# Adafruit_Feather_M0_Express_test.net
KiCad netlist of a schematic drawn in EAGLE
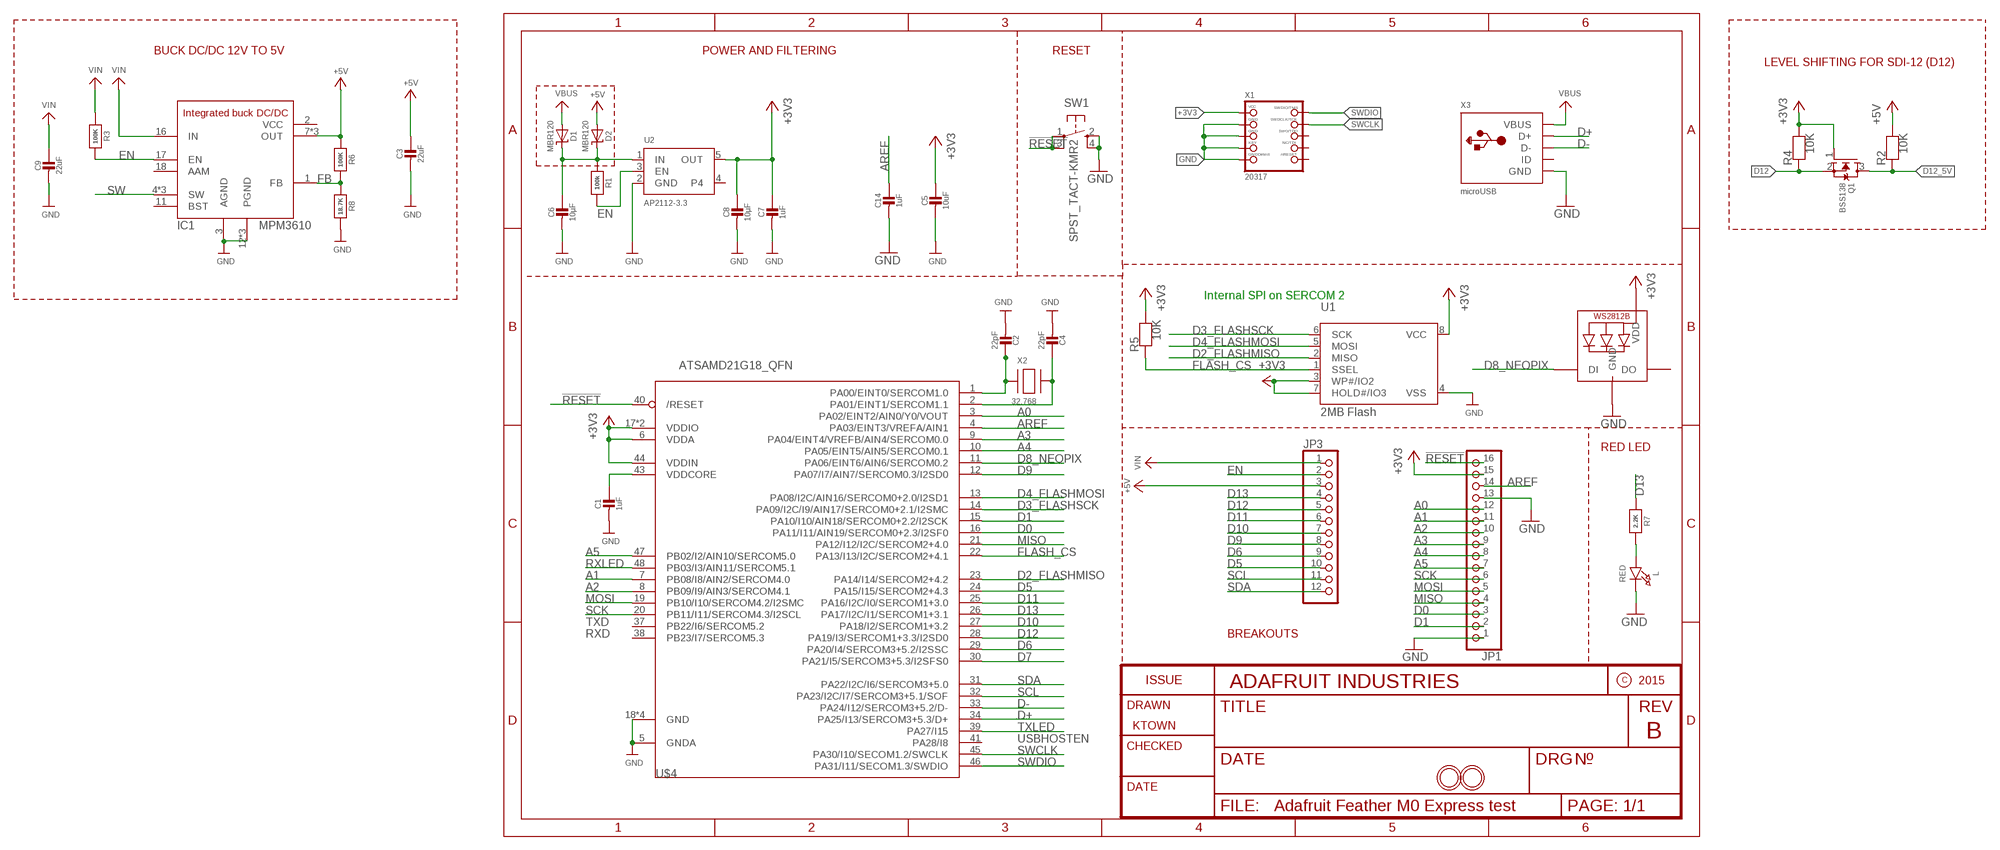
[diagram p0: schematic, sheet 1]

(export (version "E")
  (design (tool "Eeschema 10.0.6"))
  (components
    (comp (ref "C1")
      (value "1uF")
      (footprint "eagle-import:0603-NO")
      (libsource (lib "eagle-import") (part "CAP_CERAMIC0603_NO"))
    )
    (comp (ref "C2")
      (value "22pF")
      (footprint "eagle-import:0603-NO")
      (libsource (lib "eagle-import") (part "CAP_CERAMIC0603_NO"))
    )
    (comp (ref "C3")
      (value "22uF")
      (footprint "eagle-import:0805-NO")
      (libsource (lib "eagle-import") (part "CAP_CERAMIC0805-NOOUTLINE"))
    )
    (comp (ref "C4")
      (value "22pF")
      (footprint "eagle-import:0603-NO")
      (libsource (lib "eagle-import") (part "CAP_CERAMIC0603_NO"))
    )
    (comp (ref "C5")
      (value "10uF")
      (footprint "eagle-import:0805-NO")
      (libsource (lib "eagle-import") (part "CAP_CERAMIC0805-NOOUTLINE"))
    )
    (comp (ref "C6")
      (value "10µF")
      (footprint "eagle-import:0805-NO")
      (libsource (lib "eagle-import") (part "CAP_CERAMIC0805-NOOUTLINE"))
    )
    (comp (ref "C7")
      (value "1uF")
      (footprint "eagle-import:0603-NO")
      (libsource (lib "eagle-import") (part "CAP_CERAMIC0603_NO"))
    )
    (comp (ref "C8")
      (value "10µF")
      (footprint "eagle-import:0805-NO")
      (libsource (lib "eagle-import") (part "CAP_CERAMIC0805-NOOUTLINE"))
    )
    (comp (ref "C9")
      (value "22uF")
      (footprint "eagle-import:0805-NO")
      (libsource (lib "eagle-import") (part "CAP_CERAMIC0805-NOOUTLINE"))
    )
    (comp (ref "C14")
      (value "1uF")
      (footprint "eagle-import:0603-NO")
      (libsource (lib "eagle-import") (part "CAP_CERAMIC0603_NO"))
    )
    (comp (ref "D1")
      (value "MBR120")
      (footprint "eagle-import:SOD-123")
      (libsource (lib "eagle-import") (part "DIODE-SCHOTTKYSOD-123"))
    )
    (comp (ref "D2")
      (value "MBR120")
      (footprint "eagle-import:SOD-123")
      (libsource (lib "eagle-import") (part "DIODE-SCHOTTKYSOD-123"))
    )
    (comp (ref "IC1")
      (value "MPM3610")
      (footprint "eagle-import:MPM3610")
      (libsource (lib "eagle-import") (part "MPM3610"))
    )
    (comp (ref "JP1")
      (value "HEADER-1X16ROUND")
      (footprint "eagle-import:1X16_ROUND")
      (libsource (lib "eagle-import") (part "HEADER-1X16ROUND"))
    )
    (comp (ref "JP3")
      (value "HEADER-1X12")
      (footprint "eagle-import:1X12_ROUND")
      (libsource (lib "eagle-import") (part "HEADER-1X12"))
    )
    (comp (ref "L")
      (value "RED")
      (footprint "eagle-import:CHIPLED_0805_NOOUTLINE")
      (libsource (lib "eagle-import") (part "LED0805_NOOUTLINE"))
    )
    (comp (ref "LED1")
      (value "WS2812B3535")
      (footprint "eagle-import:LED3535")
      (libsource (lib "eagle-import") (part "WS2812B3535"))
    )
    (comp (ref "Q1")
      (value "BSS138")
      (footprint "eagle-import:SOT23")
      (libsource (lib "eagle-import") (part "MOSFET-NREFLOW"))
    )
    (comp (ref "R1")
      (value "100k")
      (footprint "eagle-import:0603-NO")
      (libsource (lib "eagle-import") (part "RESISTOR_0603_NOOUT"))
    )
    (comp (ref "R2")
      (value "10K")
      (footprint "eagle-import:0603-NO")
      (libsource (lib "eagle-import") (part "RESISTOR_0603_NOOUT"))
    )
    (comp (ref "R3")
      (value "100K")
      (footprint "eagle-import:0603-NO")
      (libsource (lib "eagle-import") (part "RESISTOR_0603_NOOUT"))
    )
    (comp (ref "R4")
      (value "10K")
      (footprint "eagle-import:0603-NO")
      (libsource (lib "eagle-import") (part "RESISTOR_0603_NOOUT"))
    )
    (comp (ref "R5")
      (value "10K")
      (footprint "eagle-import:0603-NO")
      (libsource (lib "eagle-import") (part "RESISTOR_0603_NOOUT"))
    )
    (comp (ref "R6")
      (value "100K")
      (footprint "eagle-import:0603-NO")
      (libsource (lib "eagle-import") (part "RESISTOR_0603_NOOUT"))
    )
    (comp (ref "R7")
      (value "2.2K")
      (footprint "eagle-import:0603-NO")
      (libsource (lib "eagle-import") (part "RESISTOR_0603_NOOUT"))
    )
    (comp (ref "R8")
      (value "18.7K")
      (footprint "eagle-import:0603-NO")
      (libsource (lib "eagle-import") (part "RESISTOR_0603_NOOUT"))
    )
    (comp (ref "SW1")
      (value "SPST_TACT-KMR2")
      (footprint "eagle-import:KMR2")
      (libsource (lib "eagle-import") (part "SPST_TACT-KMR2"))
    )
    (comp (ref "U$4")
      (value "ATSAMD21G18_QFN")
      (footprint "eagle-import:TQFN48_7MM")
      (libsource (lib "eagle-import") (part "ATSAMD21G_QFN"))
    )
    (comp (ref "U$31")
      (value "MOUNTINGHOLE2.5")
      (footprint "eagle-import:MOUNTINGHOLE_2.5_PLATED")
      (libsource (lib "eagle-import") (part "MOUNTINGHOLE2.5"))
    )
    (comp (ref "U$32")
      (value "MOUNTINGHOLE2.5")
      (footprint "eagle-import:MOUNTINGHOLE_2.5_PLATED")
      (libsource (lib "eagle-import") (part "MOUNTINGHOLE2.5"))
    )
    (comp (ref "U1")
      (value "2MB Flash")
      (footprint "eagle-import:SOIC8_208MIL")
      (libsource (lib "eagle-import") (part "SPIFLASH_SOIC8208MIL"))
    )
    (comp (ref "U2")
      (value "AP2112-3.3")
      (footprint "eagle-import:SOT23-5")
      (libsource (lib "eagle-import") (part "VREG_SOT23-5"))
    )
    (comp (ref "X1")
      (value "20317")
      (footprint "eagle-import:2X05_1.27MM_BOX_POSTS")
      (libsource (lib "eagle-import") (part "JTAG-CORTEXBOXPOSTS"))
    )
    (comp (ref "X2")
      (value "32.768")
      (footprint "eagle-import:XTAL3215")
      (libsource (lib "eagle-import") (part "XTAL-3.2X1.5"))
    )
    (comp (ref "X3")
      (value "microUSB")
      (footprint "eagle-import:4UCONN_20329_V2")
      (libsource (lib "eagle-import") (part "USB_MICRO_20329_V2"))
    )
  )
  (nets
    (net (code "1") (name "+3V3") (class "Default")
      (node (ref "C5") (pin "1") (pinfunction "1_1") (pintype "passive"))
      (node (ref "C7") (pin "1") (pinfunction "1_1") (pintype "passive"))
      (node (ref "C8") (pin "1") (pinfunction "1_1") (pintype "passive"))
      (node (ref "JP1") (pin "15") (pinfunction "15_15") (pintype "passive"))
      (node (ref "LED1") (pin "2") (pinfunction "VDD_2") (pintype "power_in"))
      (node (ref "Q1") (pin "1") (pinfunction "G_1") (pintype "bidirectional"))
      (node (ref "R4") (pin "2") (pinfunction "2_2") (pintype "passive"))
      (node (ref "R5") (pin "2") (pinfunction "2_2") (pintype "passive"))
      (node (ref "U$4") (pin "17") (pinfunction "VDDIO_17") (pintype "power_in"))
      (node (ref "U$4") (pin "36") (pinfunction "VDDIO_36") (pintype "power_in"))
      (node (ref "U$4") (pin "44") (pinfunction "VDDIN_44") (pintype "power_in"))
      (node (ref "U$4") (pin "6") (pinfunction "VDDA_6") (pintype "power_in"))
      (node (ref "U1") (pin "3") (pinfunction "WP#/IO2_3") (pintype "bidirectional"))
      (node (ref "U1") (pin "7") (pinfunction "HOLD#/IO3_7") (pintype "bidirectional"))
      (node (ref "U1") (pin "8") (pinfunction "VCC_8") (pintype "bidirectional"))
      (node (ref "U2") (pin "5") (pinfunction "OUT_5") (pintype "power_in"))
      (node (ref "X1") (pin "1") (pinfunction "VCC_1") (pintype "power_in"))
    )
    (net (code "2") (name "+5V") (class "Default")
      (node (ref "C3") (pin "1") (pinfunction "1_1") (pintype "passive"))
      (node (ref "D2") (pin "A") (pinfunction "A_A") (pintype "passive"))
      (node (ref "IC1") (pin "7") (pinfunction "OUT_7") (pintype "power_in"))
      (node (ref "IC1") (pin "8") (pinfunction "OUT_8") (pintype "power_in"))
      (node (ref "IC1") (pin "9") (pinfunction "OUT_9") (pintype "power_in"))
      (node (ref "JP3") (pin "3") (pinfunction "3_3") (pintype "passive"))
      (node (ref "R2") (pin "2") (pinfunction "2_2") (pintype "passive"))
      (node (ref "R6") (pin "1") (pinfunction "1_1") (pintype "passive"))
    )
    (net (code "3") (name "/A0") (class "Default")
      (node (ref "JP1") (pin "12") (pinfunction "12_12") (pintype "passive"))
      (node (ref "U$4") (pin "3") (pinfunction "PA02/EINT2/AIN0/Y0/VOUT_3") (pintype "bidirectional"))
    )
    (net (code "4") (name "/A1") (class "Default")
      (node (ref "JP1") (pin "11") (pinfunction "11_11") (pintype "passive"))
      (node (ref "U$4") (pin "7") (pinfunction "PB08/I8/AIN2/SERCOM4.0_7") (pintype "bidirectional"))
    )
    (net (code "5") (name "/A2") (class "Default")
      (node (ref "JP1") (pin "10") (pinfunction "10_10") (pintype "passive"))
      (node (ref "U$4") (pin "8") (pinfunction "PB09/I9/AIN3/SERCOM4.1_8") (pintype "bidirectional"))
    )
    (net (code "6") (name "/A3") (class "Default")
      (node (ref "JP1") (pin "9") (pinfunction "9_9") (pintype "passive"))
      (node (ref "U$4") (pin "9") (pinfunction "PA04/EINT4/VREFB/AIN4/SERCOM0.0_9") (pintype "bidirectional"))
    )
    (net (code "7") (name "/A4") (class "Default")
      (node (ref "JP1") (pin "8") (pinfunction "8_8") (pintype "passive"))
      (node (ref "U$4") (pin "10") (pinfunction "PA05/EINT5/AIN5/SERCOM0.1_10") (pintype "bidirectional"))
    )
    (net (code "8") (name "/A5") (class "Default")
      (node (ref "JP1") (pin "7") (pinfunction "7_7") (pintype "passive"))
      (node (ref "U$4") (pin "47") (pinfunction "PB02/I2/AIN10/SERCOM5.0_47") (pintype "bidirectional"))
    )
    (net (code "9") (name "/AREF") (class "Default")
      (node (ref "C14") (pin "1") (pinfunction "1_1") (pintype "passive"))
      (node (ref "JP1") (pin "14") (pinfunction "14_14") (pintype "passive"))
      (node (ref "U$4") (pin "4") (pinfunction "PA03/EINT3/VREFA/AIN1_4") (pintype "bidirectional"))
    )
    (net (code "10") (name "/D+") (class "Default")
      (node (ref "U$4") (pin "34") (pinfunction "PA25/I13/SERCOM3+5.3/D+_34") (pintype "bidirectional"))
      (node (ref "X3") (pin "D+") (pinfunction "D+_D+") (pintype "bidirectional"))
    )
    (net (code "11") (name "/D-") (class "Default")
      (node (ref "U$4") (pin "33") (pinfunction "PA24/I12/SERCOM3+5.2/D-_33") (pintype "bidirectional"))
      (node (ref "X3") (pin "D-") (pinfunction "D-_D-") (pintype "bidirectional"))
    )
    (net (code "12") (name "/D0") (class "Default")
      (node (ref "JP1") (pin "3") (pinfunction "3_3") (pintype "passive"))
      (node (ref "U$4") (pin "16") (pinfunction "PA11/I11/AIN19/SERCOM0+2.3/I2SF0_16") (pintype "bidirectional"))
    )
    (net (code "13") (name "/D1") (class "Default")
      (node (ref "JP1") (pin "2") (pinfunction "2_2") (pintype "passive"))
      (node (ref "U$4") (pin "15") (pinfunction "PA10/I10/AIN18/SERCOM0+2.2/I2SCK_15") (pintype "bidirectional"))
    )
    (net (code "14") (name "/D2_FLASHMISO") (class "Default")
      (node (ref "U$4") (pin "23") (pinfunction "PA14/I14/SERCOM2+4.2_23") (pintype "bidirectional"))
      (node (ref "U1") (pin "2") (pinfunction "MISO_2") (pintype "bidirectional"))
    )
    (net (code "15") (name "/D3_FLASHSCK") (class "Default")
      (node (ref "U$4") (pin "14") (pinfunction "PA09/I2C/I9/AIN17/SERCOM0+2.1/I2SMC_14") (pintype "bidirectional"))
      (node (ref "U1") (pin "6") (pinfunction "SCK_6") (pintype "bidirectional"))
    )
    (net (code "16") (name "/D4_FLASHMOSI") (class "Default")
      (node (ref "U$4") (pin "13") (pinfunction "PA08/I2C/AIN16/SERCOM0+2.0/I2SD1_13") (pintype "bidirectional"))
      (node (ref "U1") (pin "5") (pinfunction "MOSI_5") (pintype "bidirectional"))
    )
    (net (code "17") (name "/D5") (class "Default")
      (node (ref "JP3") (pin "10") (pinfunction "10_10") (pintype "passive"))
      (node (ref "U$4") (pin "24") (pinfunction "PA15/I15/SERCOM2+4.3_24") (pintype "bidirectional"))
    )
    (net (code "18") (name "/D6") (class "Default")
      (node (ref "JP3") (pin "9") (pinfunction "9_9") (pintype "passive"))
      (node (ref "U$4") (pin "29") (pinfunction "PA20/I4/SERCOM3+5.2/I2SSC_29") (pintype "bidirectional"))
    )
    (net (code "19") (name "/D7") (class "Default")
      (node (ref "U$4") (pin "30") (pinfunction "PA21/I5/SERCOM3+5.3/I2SFS0_30") (pintype "bidirectional"))
    )
    (net (code "20") (name "/D8_NEOPIX") (class "Default")
      (node (ref "LED1") (pin "1") (pinfunction "DI_1") (pintype "input"))
      (node (ref "U$4") (pin "11") (pinfunction "PA06/EINT6/AIN6/SERCOM0.2_11") (pintype "bidirectional"))
    )
    (net (code "21") (name "/D9") (class "Default")
      (node (ref "JP3") (pin "8") (pinfunction "8_8") (pintype "passive"))
      (node (ref "U$4") (pin "12") (pinfunction "PA07/I7/AIN7/SERCOM0.3/I2SD0_12") (pintype "bidirectional"))
    )
    (net (code "22") (name "/D10") (class "Default")
      (node (ref "JP3") (pin "7") (pinfunction "7_7") (pintype "passive"))
      (node (ref "U$4") (pin "27") (pinfunction "PA18/I2/SERCOM1+3.2_27") (pintype "bidirectional"))
    )
    (net (code "23") (name "/D11") (class "Default")
      (node (ref "JP3") (pin "6") (pinfunction "6_6") (pintype "passive"))
      (node (ref "U$4") (pin "25") (pinfunction "PA16/I2C/I0/SERCOM1+3.0_25") (pintype "bidirectional"))
    )
    (net (code "24") (name "/D13") (class "Default")
      (node (ref "JP3") (pin "4") (pinfunction "4_4") (pintype "passive"))
      (node (ref "R7") (pin "1") (pinfunction "1_1") (pintype "passive"))
      (node (ref "U$4") (pin "26") (pinfunction "PA17/I2C/I1/SERCOM1+3.1_26") (pintype "bidirectional"))
    )
    (net (code "25") (name "/EN") (class "Default")
      (node (ref "IC1") (pin "17") (pinfunction "EN_17") (pintype "input"))
      (node (ref "JP3") (pin "2") (pinfunction "2_2") (pintype "passive"))
      (node (ref "R1") (pin "2") (pinfunction "2_2") (pintype "passive"))
      (node (ref "R3") (pin "2") (pinfunction "2_2") (pintype "passive"))
      (node (ref "U2") (pin "3") (pinfunction "EN_3") (pintype "input"))
    )
    (net (code "26") (name "/FB") (class "Default")
      (node (ref "IC1") (pin "1") (pinfunction "FB_1") (pintype "input"))
      (node (ref "R6") (pin "2") (pinfunction "2_2") (pintype "passive"))
      (node (ref "R8") (pin "1") (pinfunction "1_1") (pintype "passive"))
    )
    (net (code "27") (name "/FLASH_CS") (class "Default")
      (node (ref "R5") (pin "1") (pinfunction "1_1") (pintype "passive"))
      (node (ref "U$4") (pin "22") (pinfunction "PA13/I13/I2C/SERCOM2+4.1_22") (pintype "bidirectional"))
      (node (ref "U1") (pin "1") (pinfunction "SSEL_1") (pintype "bidirectional"))
    )
    (net (code "28") (name "/MISO") (class "Default")
      (node (ref "JP1") (pin "4") (pinfunction "4_4") (pintype "passive"))
      (node (ref "U$4") (pin "21") (pinfunction "PA12/I12/I2C/SERCOM2+4.0_21") (pintype "bidirectional"))
    )
    (net (code "29") (name "/MOSI") (class "Default")
      (node (ref "JP1") (pin "5") (pinfunction "5_5") (pintype "passive"))
      (node (ref "U$4") (pin "19") (pinfunction "PB10/I10/SERCOM4.2/I2SMC_19") (pintype "bidirectional"))
    )
    (net (code "30") (name "/RXLED") (class "Default")
      (node (ref "U$4") (pin "48") (pinfunction "PB03/I3/AIN11/SERCOM5.1_48") (pintype "bidirectional"))
    )
    (net (code "31") (name "/SCK") (class "Default")
      (node (ref "JP1") (pin "6") (pinfunction "6_6") (pintype "passive"))
      (node (ref "U$4") (pin "20") (pinfunction "PB11/I11/SERCOM4.3/I2SCL_20") (pintype "bidirectional"))
    )
    (net (code "32") (name "/SCL") (class "Default")
      (node (ref "JP3") (pin "11") (pinfunction "11_11") (pintype "passive"))
      (node (ref "U$4") (pin "32") (pinfunction "PA23/I2C/I7/SERCOM3+5.1/SOF_32") (pintype "bidirectional"))
    )
    (net (code "33") (name "/SDA") (class "Default")
      (node (ref "JP3") (pin "12") (pinfunction "12_12") (pintype "passive"))
      (node (ref "U$4") (pin "31") (pinfunction "PA22/I2C/I6/SERCOM3+5.0_31") (pintype "bidirectional"))
    )
    (net (code "34") (name "/SW") (class "Default")
      (node (ref "IC1") (pin "4") (pinfunction "SW_4") (pintype "passive"))
      (node (ref "IC1") (pin "5") (pinfunction "SW_5") (pintype "passive"))
      (node (ref "IC1") (pin "6") (pinfunction "SW_6") (pintype "passive"))
    )
    (net (code "35") (name "/TXLED") (class "Default")
      (node (ref "U$4") (pin "39") (pinfunction "PA27/I15_39") (pintype "bidirectional"))
    )
    (net (code "36") (name "/VCC") (class "Default")
      (node (ref "IC1") (pin "2") (pinfunction "VCC_2") (pintype "power_in"))
    )
    (net (code "37") (name "/~{RESET}") (class "Default")
      (node (ref "JP1") (pin "16") (pinfunction "16_16") (pintype "passive"))
      (node (ref "SW1") (pin "1") (pinfunction "P_1") (pintype "passive"))
      (node (ref "SW1") (pin "3") (pinfunction "P1_3") (pintype "passive"))
      (node (ref "U$4") (pin "40") (pinfunction "/RESET_40") (pintype "bidirectional"))
    )
    (net (code "38") (name "D12") (class "Default")
      (node (ref "JP3") (pin "5") (pinfunction "5_5") (pintype "passive"))
      (node (ref "Q1") (pin "2") (pinfunction "S_2") (pintype "bidirectional"))
      (node (ref "R4") (pin "1") (pinfunction "1_1") (pintype "passive"))
      (node (ref "U$4") (pin "28") (pinfunction "PA19/I3/SERCOM1+3.3/I2SD0_28") (pintype "bidirectional"))
    )
    (net (code "39") (name "D12_5V") (class "Default")
      (node (ref "Q1") (pin "3") (pinfunction "D_3") (pintype "bidirectional"))
      (node (ref "R2") (pin "1") (pinfunction "1_1") (pintype "passive"))
    )
    (net (code "40") (name "GND") (class "Default")
      (node (ref "C1") (pin "2") (pinfunction "2_2") (pintype "passive"))
      (node (ref "C14") (pin "2") (pinfunction "2_2") (pintype "passive"))
      (node (ref "C2") (pin "2") (pinfunction "2_2") (pintype "passive"))
      (node (ref "C3") (pin "2") (pinfunction "2_2") (pintype "passive"))
      (node (ref "C4") (pin "2") (pinfunction "2_2") (pintype "passive"))
      (node (ref "C5") (pin "2") (pinfunction "2_2") (pintype "passive"))
      (node (ref "C6") (pin "2") (pinfunction "2_2") (pintype "passive"))
      (node (ref "C7") (pin "2") (pinfunction "2_2") (pintype "passive"))
      (node (ref "C8") (pin "2") (pinfunction "2_2") (pintype "passive"))
      (node (ref "C9") (pin "2") (pinfunction "2_2") (pintype "passive"))
      (node (ref "IC1") (pin "12") (pinfunction "PGND_12") (pintype "power_in"))
      (node (ref "IC1") (pin "13") (pinfunction "PGND_13") (pintype "power_in"))
      (node (ref "IC1") (pin "14") (pinfunction "PGND_14") (pintype "power_in"))
      (node (ref "IC1") (pin "3") (pinfunction "AGND_3") (pintype "power_in"))
      (node (ref "JP1") (pin "1") (pinfunction "1_1") (pintype "passive"))
      (node (ref "JP1") (pin "13") (pinfunction "13_13") (pintype "passive"))
      (node (ref "L") (pin "C") (pinfunction "C_C") (pintype "passive"))
      (node (ref "LED1") (pin "4") (pinfunction "GND_4") (pintype "power_in"))
      (node (ref "R8") (pin "2") (pinfunction "2_2") (pintype "passive"))
      (node (ref "SW1") (pin "2") (pinfunction "S_2") (pintype "passive"))
      (node (ref "SW1") (pin "4") (pinfunction "S1_4") (pintype "passive"))
      (node (ref "U$4") (pin "18") (pinfunction "GND_18") (pintype "power_in"))
      (node (ref "U$4") (pin "35") (pinfunction "GND_35") (pintype "power_in"))
      (node (ref "U$4") (pin "42") (pinfunction "GND_42") (pintype "power_in"))
      (node (ref "U$4") (pin "5") (pinfunction "GNDA_5") (pintype "power_in"))
      (node (ref "U$4") (pin "THERMAL") (pinfunction "GND_THERMAL") (pintype "power_in"))
      (node (ref "U1") (pin "4") (pinfunction "VSS_4") (pintype "bidirectional"))
      (node (ref "U2") (pin "2") (pinfunction "GND_2") (pintype "power_in"))
      (node (ref "X1") (pin "3") (pinfunction "GND_3") (pintype "power_in"))
      (node (ref "X1") (pin "5") (pinfunction "GND_5") (pintype "power_in"))
      (node (ref "X1") (pin "7") (pinfunction "KEY_7") (pintype "bidirectional"))
      (node (ref "X1") (pin "9") (pinfunction "GNDDETECT_9") (pintype "bidirectional"))
      (node (ref "X3") (pin "BASE@1") (pinfunction "GND_BASE@1") (pintype "power_in"))
      (node (ref "X3") (pin "BASE@2") (pinfunction "GND_BASE@2") (pintype "power_in"))
      (node (ref "X3") (pin "GND") (pinfunction "GND_GND") (pintype "power_in"))
      (node (ref "X3") (pin "SPRT@1") (pinfunction "GND_SPRT@1") (pintype "power_in"))
      (node (ref "X3") (pin "SPRT@2") (pinfunction "GND_SPRT@2") (pintype "power_in"))
      (node (ref "X3") (pin "SPRT@3") (pinfunction "GND_SPRT@3") (pintype "power_in"))
      (node (ref "X3") (pin "SPRT@4") (pinfunction "GND_SPRT@4") (pintype "power_in"))
    )
    (net (code "41") (name "Net-(L-PadA)") (class "Default")
      (node (ref "L") (pin "A") (pinfunction "A_A") (pintype "passive"))
      (node (ref "R7") (pin "2") (pinfunction "2_2") (pintype "passive"))
    )
    (net (code "42") (name "Net-(U$4-PA00{slash}EINT0{slash}SERCOM1.0)") (class "Default")
      (node (ref "C2") (pin "1") (pinfunction "1_1") (pintype "passive"))
      (node (ref "U$4") (pin "1") (pinfunction "PA00/EINT0/SERCOM1.0_1") (pintype "bidirectional"))
      (node (ref "X2") (pin "P$1") (pinfunction "P$1_P$1") (pintype "bidirectional"))
    )
    (net (code "43") (name "Net-(U$4-PA01{slash}EINT1{slash}SERCOM1.1)") (class "Default")
      (node (ref "C4") (pin "1") (pinfunction "1_1") (pintype "passive"))
      (node (ref "U$4") (pin "2") (pinfunction "PA01/EINT1/SERCOM1.1_2") (pintype "bidirectional"))
      (node (ref "X2") (pin "P$2") (pinfunction "P$2_P$2") (pintype "bidirectional"))
    )
    (net (code "44") (name "Net-(U$4-VDDCORE)") (class "Default")
      (node (ref "C1") (pin "1") (pinfunction "1_1") (pintype "passive"))
      (node (ref "U$4") (pin "43") (pinfunction "VDDCORE_43") (pintype "power_in"))
    )
    (net (code "45") (name "Net-(U2-IN)") (class "Default")
      (node (ref "C6") (pin "1") (pinfunction "1_1") (pintype "passive"))
      (node (ref "D1") (pin "C") (pinfunction "C_C") (pintype "passive"))
      (node (ref "D2") (pin "C") (pinfunction "C_C") (pintype "passive"))
      (node (ref "R1") (pin "1") (pinfunction "1_1") (pintype "passive"))
      (node (ref "U2") (pin "1") (pinfunction "IN_1") (pintype "power_in"))
    )
    (net (code "46") (name "SWCLK") (class "Default")
      (node (ref "U$4") (pin "45") (pinfunction "PA30/I10/SECOM1.2/SWCLK_45") (pintype "bidirectional"))
      (node (ref "X1") (pin "4") (pinfunction "SWDCLK_4") (pintype "bidirectional"))
    )
    (net (code "47") (name "SWDIO") (class "Default")
      (node (ref "U$4") (pin "46") (pinfunction "PA31/I11/SECOM1.3/SWDIO_46") (pintype "bidirectional"))
      (node (ref "X1") (pin "2") (pinfunction "SWDIO_2") (pintype "bidirectional"))
    )
    (net (code "48") (name "VBUS") (class "Default")
      (node (ref "D1") (pin "A") (pinfunction "A_A") (pintype "passive"))
      (node (ref "X3") (pin "VBUS") (pinfunction "VBUS_VBUS") (pintype "power_in"))
    )
    (net (code "49") (name "VIN") (class "Default")
      (node (ref "C9") (pin "1") (pinfunction "1_1") (pintype "passive"))
      (node (ref "IC1") (pin "16") (pinfunction "IN_16") (pintype "power_in"))
      (node (ref "JP3") (pin "1") (pinfunction "1_1") (pintype "passive"))
      (node (ref "R3") (pin "1") (pinfunction "1_1") (pintype "passive"))
    )
    (net (code "50") (name "unconnected-(IC1-AAM-Pad18)") (class "Default")
      (node (ref "IC1") (pin "18") (pinfunction "AAM_18") (pintype "input"))
    )
    (net (code "51") (name "unconnected-(IC1-BST-Pad11)") (class "Default")
      (node (ref "IC1") (pin "11") (pinfunction "BST_11") (pintype "passive"))
    )
    (net (code "52") (name "unconnected-(LED1-DO-Pad3)") (class "Default")
      (node (ref "LED1") (pin "3") (pinfunction "DO_3") (pintype "output"))
    )
    (net (code "53") (name "unconnected-(U$4-PA28{slash}I8-Pad41)") (class "Default")
      (node (ref "U$4") (pin "41") (pinfunction "PA28/I8_41") (pintype "bidirectional"))
    )
    (net (code "54") (name "unconnected-(U$4-PB22{slash}I6{slash}SERCOM5.2-Pad37)") (class "Default")
      (node (ref "U$4") (pin "37") (pinfunction "PB22/I6/SERCOM5.2_37") (pintype "bidirectional"))
    )
    (net (code "55") (name "unconnected-(U$4-PB23{slash}I7{slash}SERCOM5.3-Pad38)") (class "Default")
      (node (ref "U$4") (pin "38") (pinfunction "PB23/I7/SERCOM5.3_38") (pintype "bidirectional"))
    )
    (net (code "56") (name "unconnected-(U2-P4-Pad4)") (class "Default")
      (node (ref "U2") (pin "4") (pinfunction "P4_4") (pintype "bidirectional"))
    )
    (net (code "57") (name "unconnected-(X1-NRESET-Pad10)") (class "Default")
      (node (ref "X1") (pin "10") (pinfunction "NRESET_10") (pintype "bidirectional"))
    )
    (net (code "58") (name "unconnected-(X1-SWO-Pad6)") (class "Default")
      (node (ref "X1") (pin "6") (pinfunction "SWO_6") (pintype "bidirectional"))
    )
    (net (code "59") (name "unconnected-(X1-TDI-Pad8)") (class "Default")
      (node (ref "X1") (pin "8") (pinfunction "TDI_8") (pintype "bidirectional"))
    )
    (net (code "60") (name "unconnected-(X3-PadID)") (class "Default")
      (node (ref "X3") (pin "ID") (pinfunction "ID_ID") (pintype "bidirectional"))
    )
  )
)
